# MoodBadge.net
KiCad netlist of a schematic drawn in EAGLE
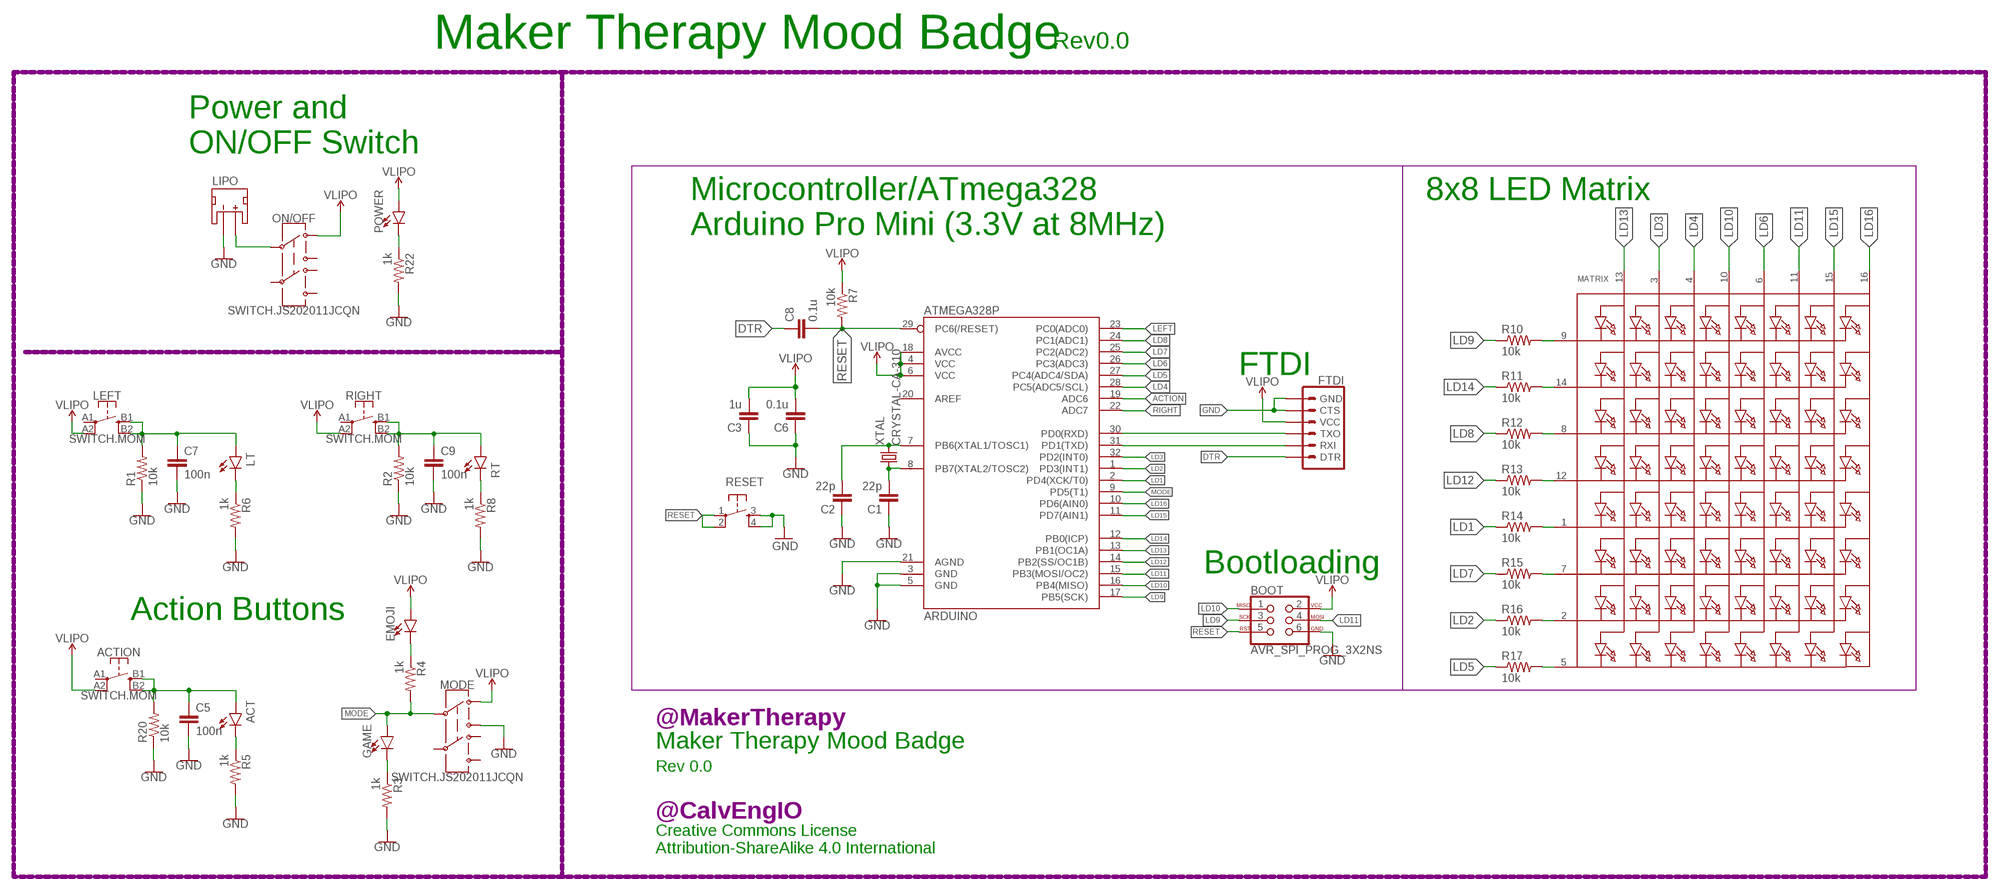
[diagram p0: schematic, sheet 1]

(export (version "E")
  (design (tool "Eeschema 10.0.6"))
  (components
    (comp (ref "ACT")
      (value "LED0603")
      (footprint "eagle-import:LED-0603")
      (libsource (lib "eagle-import") (part "LED0603"))
    )
    (comp (ref "ACTION")
      (value "SWITCH.MOM")
      (footprint "eagle-import:TACTILE_SWITCH_SMD_6.2MM_TALL")
      (libsource (lib "eagle-import") (part "SWITCH.MOM"))
    )
    (comp (ref "ARDUINO")
      (value "ATMEGA328P")
      (footprint "eagle-import:TQFP32-08")
      (libsource (lib "eagle-import") (part "ATMEGA328_SMT-OHMOD"))
    )
    (comp (ref "BOOT")
      (value "AVR_SPI_PROG_3X2NS")
      (footprint "eagle-import:2X3-NS")
      (libsource (lib "eagle-import") (part "AVR_SPI_PROG_3X2NS"))
    )
    (comp (ref "C1")
      (value "22p")
      (footprint "eagle-import:C0402")
      (libsource (lib "eagle-import") (part "CAPACITOR0402"))
    )
    (comp (ref "C2")
      (value "22p")
      (footprint "eagle-import:C0402")
      (libsource (lib "eagle-import") (part "CAPACITOR0402"))
    )
    (comp (ref "C3")
      (value "1u")
      (footprint "eagle-import:C0402")
      (libsource (lib "eagle-import") (part "CAPACITOR0402"))
    )
    (comp (ref "C5")
      (value "100n")
      (footprint "eagle-import:C0402")
      (libsource (lib "eagle-import") (part "CAPACITOR0402"))
    )
    (comp (ref "C6")
      (value "0.1u")
      (footprint "eagle-import:C0402")
      (libsource (lib "eagle-import") (part "CAPACITOR0402"))
    )
    (comp (ref "C7")
      (value "100n")
      (footprint "eagle-import:C0402")
      (libsource (lib "eagle-import") (part "CAPACITOR0402"))
    )
    (comp (ref "C8")
      (value "0.1u")
      (footprint "eagle-import:C0402")
      (libsource (lib "eagle-import") (part "C-EUC0402"))
    )
    (comp (ref "C9")
      (value "100n")
      (footprint "eagle-import:C0402")
      (libsource (lib "eagle-import") (part "CAPACITOR0402"))
    )
    (comp (ref "EMOJI")
      (value "LED0603")
      (footprint "eagle-import:LED-0603")
      (libsource (lib "eagle-import") (part "LED0603"))
    )
    (comp (ref "FTDI")
      (value "6_PIN_SERIAL_TARGETSILK")
      (footprint "eagle-import:6_PIN_SERIAL_TARGET_SIDE_W_SILK")
      (libsource (lib "eagle-import") (part "6_PIN_SERIAL_TARGETSILK"))
    )
    (comp (ref "GAME")
      (value "LED0603")
      (footprint "eagle-import:LED-0603")
      (libsource (lib "eagle-import") (part "LED0603"))
    )
    (comp (ref "LEFT")
      (value "SWITCH.MOM")
      (footprint "eagle-import:TACTILE_SWITCH_SMD_6.2MM_TALL")
      (libsource (lib "eagle-import") (part "SWITCH.MOM"))
    )
    (comp (ref "LIPO")
      (value "JST_2MM_MALE")
      (footprint "eagle-import:JST-2-SMD")
      (libsource (lib "eagle-import") (part "JST_2MM_MALE"))
    )
    (comp (ref "LT")
      (value "LED0603")
      (footprint "eagle-import:LED-0603")
      (libsource (lib "eagle-import") (part "LED0603"))
    )
    (comp (ref "MATRIX")
      (value "SEGMENT_8X8_ROWCATHODEM12A881UR")
      (footprint "eagle-import:SEGMENT_BL-M12A881UR")
      (libsource (lib "eagle-import") (part "SEGMENT_8X8_ROWCATHODEM12A881UR"))
    )
    (comp (ref "MODE")
      (value "SWITCH.JS202011JCQN")
      (footprint "eagle-import:SWITCH.00")
      (libsource (lib "eagle-import") (part "SWITCH.JS202011JCQN"))
    )
    (comp (ref "ON/OFF")
      (value "SWITCH.JS202011JCQN")
      (footprint "eagle-import:SWITCH.00")
      (libsource (lib "eagle-import") (part "SWITCH.JS202011JCQN"))
    )
    (comp (ref "POWER")
      (value "LED5MM")
      (footprint "eagle-import:LED_5MM")
      (libsource (lib "eagle-import") (part "LED5MM"))
    )
    (comp (ref "R1")
      (value "10k")
      (footprint "eagle-import:R0402")
      (libsource (lib "eagle-import") (part "RESISTOR0402"))
    )
    (comp (ref "R2")
      (value "10k")
      (footprint "eagle-import:R0402")
      (libsource (lib "eagle-import") (part "RESISTOR0402"))
    )
    (comp (ref "R3")
      (value "1k")
      (footprint "eagle-import:R0402")
      (libsource (lib "eagle-import") (part "RESISTOR0402"))
    )
    (comp (ref "R4")
      (value "1k")
      (footprint "eagle-import:R0402")
      (libsource (lib "eagle-import") (part "RESISTOR0402"))
    )
    (comp (ref "R5")
      (value "1k")
      (footprint "eagle-import:R0402")
      (libsource (lib "eagle-import") (part "RESISTOR0402"))
    )
    (comp (ref "R6")
      (value "1k")
      (footprint "eagle-import:R0402")
      (libsource (lib "eagle-import") (part "RESISTOR0402"))
    )
    (comp (ref "R7")
      (value "10k")
      (footprint "eagle-import:R0402")
      (libsource (lib "eagle-import") (part "RESISTOR0402"))
    )
    (comp (ref "R8")
      (value "1k")
      (footprint "eagle-import:R0402")
      (libsource (lib "eagle-import") (part "RESISTOR0402"))
    )
    (comp (ref "R10")
      (value "10k")
      (footprint "eagle-import:R0402")
      (libsource (lib "eagle-import") (part "RESISTOR0402"))
    )
    (comp (ref "R11")
      (value "10k")
      (footprint "eagle-import:R0402")
      (libsource (lib "eagle-import") (part "RESISTOR0402"))
    )
    (comp (ref "R12")
      (value "10k")
      (footprint "eagle-import:R0402")
      (libsource (lib "eagle-import") (part "RESISTOR0402"))
    )
    (comp (ref "R13")
      (value "10k")
      (footprint "eagle-import:R0402")
      (libsource (lib "eagle-import") (part "RESISTOR0402"))
    )
    (comp (ref "R14")
      (value "10k")
      (footprint "eagle-import:R0402")
      (libsource (lib "eagle-import") (part "RESISTOR0402"))
    )
    (comp (ref "R15")
      (value "10k")
      (footprint "eagle-import:R0402")
      (libsource (lib "eagle-import") (part "RESISTOR0402"))
    )
    (comp (ref "R16")
      (value "10k")
      (footprint "eagle-import:R0402")
      (libsource (lib "eagle-import") (part "RESISTOR0402"))
    )
    (comp (ref "R17")
      (value "10k")
      (footprint "eagle-import:R0402")
      (libsource (lib "eagle-import") (part "RESISTOR0402"))
    )
    (comp (ref "R20")
      (value "10k")
      (footprint "eagle-import:R0402")
      (libsource (lib "eagle-import") (part "RESISTOR0402"))
    )
    (comp (ref "R22")
      (value "1k")
      (footprint "eagle-import:R0402")
      (libsource (lib "eagle-import") (part "RESISTOR0402"))
    )
    (comp (ref "RESET")
      (value "BUTTON-PTS830GG140")
      (footprint "eagle-import:BUTTON-GULLWING")
      (libsource (lib "eagle-import") (part "BUTTON-PTS830GG140"))
    )
    (comp (ref "RIGHT")
      (value "SWITCH.MOM")
      (footprint "eagle-import:TACTILE_SWITCH_SMD_6.2MM_TALL")
      (libsource (lib "eagle-import") (part "SWITCH.MOM"))
    )
    (comp (ref "RT")
      (value "LED0603")
      (footprint "eagle-import:LED-0603")
      (libsource (lib "eagle-import") (part "LED0603"))
    )
    (comp (ref "U$8")
      (value "CALVENGIO_HANDLEHANDLE.05")
      (footprint "eagle-import:CALVENGIO_HANDLE.05")
      (libsource (lib "eagle-import") (part "CALVENGIO_HANDLEHANDLE.05"))
    )
    (comp (ref "U$10")
      (value "MAKERTHERAPY.HANDLEMAKERTHERAPY.HANDLE.175")
      (footprint "eagle-import:MAKERTHERAPY.HANDLE.175")
      (libsource (lib "eagle-import") (part "MAKERTHERAPY.HANDLEMAKERTHERAPY.HANDLE.175"))
    )
    (comp (ref "XTAL")
      (value "CRYSTAL-CA-310")
      (footprint "eagle-import:CA-301")
      (libsource (lib "eagle-import") (part "CRYSTAL-CA-310"))
    )
  )
  (nets
    (net (code "1") (name "ACTION") (class "Default")
      (node (ref "ACT") (pin "A") (pinfunction "A_A") (pintype "passive"))
      (node (ref "ACTION") (pin "B1") (pinfunction "3_B1") (pintype "passive"))
      (node (ref "ACTION") (pin "B2") (pinfunction "4_B2") (pintype "passive"))
      (node (ref "ARDUINO") (pin "19") (pinfunction "ADC6_19") (pintype "bidirectional"))
      (node (ref "C5") (pin "1") (pinfunction "1_1") (pintype "passive"))
      (node (ref "R20") (pin "2") (pinfunction "2_2") (pintype "passive"))
    )
    (net (code "2") (name "DTR") (class "Default")
      (node (ref "C8") (pin "1") (pinfunction "1_1") (pintype "passive"))
      (node (ref "FTDI") (pin "P$1") (pinfunction "DTR_P$1") (pintype "passive"))
    )
    (net (code "3") (name "GND") (class "Default")
      (node (ref "ARDUINO") (pin "21") (pinfunction "AGND_21") (pintype "bidirectional"))
      (node (ref "ARDUINO") (pin "3") (pinfunction "GND_3") (pintype "bidirectional"))
      (node (ref "ARDUINO") (pin "5") (pinfunction "GND_5") (pintype "bidirectional"))
      (node (ref "BOOT") (pin "6") (pinfunction "6_6") (pintype "passive"))
      (node (ref "C1") (pin "1") (pinfunction "1_1") (pintype "passive"))
      (node (ref "C2") (pin "1") (pinfunction "1_1") (pintype "passive"))
      (node (ref "C3") (pin "1") (pinfunction "1_1") (pintype "passive"))
      (node (ref "C5") (pin "2") (pinfunction "2_2") (pintype "passive"))
      (node (ref "C6") (pin "1") (pinfunction "1_1") (pintype "passive"))
      (node (ref "C7") (pin "2") (pinfunction "2_2") (pintype "passive"))
      (node (ref "C9") (pin "2") (pinfunction "2_2") (pintype "passive"))
      (node (ref "FTDI") (pin "P$5") (pinfunction "CTS_P$5") (pintype "passive"))
      (node (ref "FTDI") (pin "P$6") (pinfunction "GND_P$6") (pintype "passive"))
      (node (ref "LIPO") (pin "1") (pinfunction "-_1") (pintype "bidirectional"))
      (node (ref "MODE") (pin "3") (pinfunction "3_3") (pintype "bidirectional"))
      (node (ref "R1") (pin "1") (pinfunction "1_1") (pintype "passive"))
      (node (ref "R2") (pin "1") (pinfunction "1_1") (pintype "passive"))
      (node (ref "R20") (pin "1") (pinfunction "1_1") (pintype "passive"))
      (node (ref "R22") (pin "2") (pinfunction "2_2") (pintype "passive"))
      (node (ref "R3") (pin "2") (pinfunction "2_2") (pintype "passive"))
      (node (ref "R5") (pin "2") (pinfunction "2_2") (pintype "passive"))
      (node (ref "R6") (pin "2") (pinfunction "2_2") (pintype "passive"))
      (node (ref "R8") (pin "2") (pinfunction "2_2") (pintype "passive"))
      (node (ref "RESET") (pin "3") (pinfunction "3_3") (pintype "passive"))
      (node (ref "RESET") (pin "4") (pinfunction "4_4") (pintype "passive"))
    )
    (net (code "4") (name "LD1") (class "Default")
      (node (ref "ARDUINO") (pin "2") (pinfunction "PD4(XCK/T0)_2") (pintype "bidirectional"))
      (node (ref "R14") (pin "1") (pinfunction "1_1") (pintype "passive"))
    )
    (net (code "5") (name "LD2") (class "Default")
      (node (ref "ARDUINO") (pin "1") (pinfunction "PD3(INT1)_1") (pintype "bidirectional"))
      (node (ref "R16") (pin "1") (pinfunction "1_1") (pintype "passive"))
    )
    (net (code "6") (name "LD3") (class "Default")
      (node (ref "ARDUINO") (pin "32") (pinfunction "PD2(INT0)_32") (pintype "bidirectional"))
      (node (ref "MATRIX") (pin "3") (pinfunction "A2_3") (pintype "bidirectional"))
    )
    (net (code "7") (name "LD4") (class "Default")
      (node (ref "ARDUINO") (pin "28") (pinfunction "PC5(ADC5/SCL)_28") (pintype "bidirectional"))
      (node (ref "MATRIX") (pin "4") (pinfunction "A3_4") (pintype "bidirectional"))
    )
    (net (code "8") (name "LD5") (class "Default")
      (node (ref "ARDUINO") (pin "27") (pinfunction "PC4(ADC4/SDA)_27") (pintype "bidirectional"))
      (node (ref "R17") (pin "1") (pinfunction "1_1") (pintype "passive"))
    )
    (net (code "9") (name "LD6") (class "Default")
      (node (ref "ARDUINO") (pin "26") (pinfunction "PC3(ADC3)_26") (pintype "bidirectional"))
      (node (ref "MATRIX") (pin "6") (pinfunction "A5_6") (pintype "bidirectional"))
    )
    (net (code "10") (name "LD7") (class "Default")
      (node (ref "ARDUINO") (pin "25") (pinfunction "PC2(ADC2)_25") (pintype "bidirectional"))
      (node (ref "R15") (pin "1") (pinfunction "1_1") (pintype "passive"))
    )
    (net (code "11") (name "LD8") (class "Default")
      (node (ref "ARDUINO") (pin "24") (pinfunction "PC1(ADC1)_24") (pintype "bidirectional"))
      (node (ref "R12") (pin "1") (pinfunction "1_1") (pintype "passive"))
    )
    (net (code "12") (name "LD9") (class "Default")
      (node (ref "ARDUINO") (pin "17") (pinfunction "PB5(SCK)_17") (pintype "bidirectional"))
      (node (ref "BOOT") (pin "3") (pinfunction "3_3") (pintype "passive"))
      (node (ref "R10") (pin "1") (pinfunction "1_1") (pintype "passive"))
    )
    (net (code "13") (name "LD10") (class "Default")
      (node (ref "ARDUINO") (pin "16") (pinfunction "PB4(MISO)_16") (pintype "bidirectional"))
      (node (ref "BOOT") (pin "1") (pinfunction "1_1") (pintype "passive"))
      (node (ref "MATRIX") (pin "10") (pinfunction "A4_10") (pintype "bidirectional"))
    )
    (net (code "14") (name "LD11") (class "Default")
      (node (ref "ARDUINO") (pin "15") (pinfunction "PB3(MOSI/OC2)_15") (pintype "bidirectional"))
      (node (ref "BOOT") (pin "4") (pinfunction "4_4") (pintype "passive"))
      (node (ref "MATRIX") (pin "11") (pinfunction "A6_11") (pintype "bidirectional"))
    )
    (net (code "15") (name "LD12") (class "Default")
      (node (ref "ARDUINO") (pin "14") (pinfunction "PB2(SS/OC1B)_14") (pintype "bidirectional"))
      (node (ref "R13") (pin "1") (pinfunction "1_1") (pintype "passive"))
    )
    (net (code "16") (name "LD13") (class "Default")
      (node (ref "ARDUINO") (pin "13") (pinfunction "PB1(OC1A)_13") (pintype "bidirectional"))
      (node (ref "MATRIX") (pin "13") (pinfunction "A1_13") (pintype "bidirectional"))
    )
    (net (code "17") (name "LD14") (class "Default")
      (node (ref "ARDUINO") (pin "12") (pinfunction "PB0(ICP)_12") (pintype "bidirectional"))
      (node (ref "R11") (pin "1") (pinfunction "1_1") (pintype "passive"))
    )
    (net (code "18") (name "LD15") (class "Default")
      (node (ref "ARDUINO") (pin "11") (pinfunction "PD7(AIN1)_11") (pintype "bidirectional"))
      (node (ref "MATRIX") (pin "15") (pinfunction "A7_15") (pintype "bidirectional"))
    )
    (net (code "19") (name "LD16") (class "Default")
      (node (ref "ARDUINO") (pin "10") (pinfunction "PD6(AIN0)_10") (pintype "bidirectional"))
      (node (ref "MATRIX") (pin "16") (pinfunction "A8_16") (pintype "bidirectional"))
    )
    (net (code "20") (name "LEFT") (class "Default")
      (node (ref "ARDUINO") (pin "23") (pinfunction "PC0(ADC0)_23") (pintype "bidirectional"))
      (node (ref "C7") (pin "1") (pinfunction "1_1") (pintype "passive"))
      (node (ref "LEFT") (pin "B1") (pinfunction "3_B1") (pintype "passive"))
      (node (ref "LEFT") (pin "B2") (pinfunction "4_B2") (pintype "passive"))
      (node (ref "LT") (pin "A") (pinfunction "A_A") (pintype "passive"))
      (node (ref "R1") (pin "2") (pinfunction "2_2") (pintype "passive"))
    )
    (net (code "21") (name "MODE") (class "Default")
      (node (ref "ARDUINO") (pin "9") (pinfunction "PD5(T1)_9") (pintype "bidirectional"))
      (node (ref "GAME") (pin "A") (pinfunction "A_A") (pintype "passive"))
      (node (ref "MODE") (pin "2") (pinfunction "2_2") (pintype "bidirectional"))
      (node (ref "R4") (pin "2") (pinfunction "2_2") (pintype "passive"))
    )
    (net (code "22") (name "Net-(ACT-PadC)") (class "Default")
      (node (ref "ACT") (pin "C") (pinfunction "C_C") (pintype "passive"))
      (node (ref "R5") (pin "1") (pinfunction "1_1") (pintype "passive"))
    )
    (net (code "23") (name "Net-(ARDUINO-PB6(XTAL1{slash}TOSC1))") (class "Default")
      (node (ref "ARDUINO") (pin "7") (pinfunction "PB6(XTAL1/TOSC1)_7") (pintype "bidirectional"))
      (node (ref "C2") (pin "2") (pinfunction "2_2") (pintype "passive"))
      (node (ref "XTAL") (pin "2") (pinfunction "2_2") (pintype "passive"))
    )
    (net (code "24") (name "Net-(ARDUINO-PB7(XTAL2{slash}TOSC2))") (class "Default")
      (node (ref "ARDUINO") (pin "8") (pinfunction "PB7(XTAL2/TOSC2)_8") (pintype "bidirectional"))
      (node (ref "C1") (pin "2") (pinfunction "2_2") (pintype "passive"))
      (node (ref "XTAL") (pin "1") (pinfunction "1_1") (pintype "passive"))
    )
    (net (code "25") (name "Net-(ARDUINO-PD0(RXD))") (class "Default")
      (node (ref "ARDUINO") (pin "30") (pinfunction "PD0(RXD)_30") (pintype "bidirectional"))
      (node (ref "FTDI") (pin "P$2") (pinfunction "TXO_P$2") (pintype "passive"))
    )
    (net (code "26") (name "Net-(ARDUINO-PD1(TXD))") (class "Default")
      (node (ref "ARDUINO") (pin "31") (pinfunction "PD1(TXD)_31") (pintype "bidirectional"))
      (node (ref "FTDI") (pin "P$3") (pinfunction "RXI_P$3") (pintype "passive"))
    )
    (net (code "27") (name "Net-(EMOJI-PadC)") (class "Default")
      (node (ref "EMOJI") (pin "C") (pinfunction "C_C") (pintype "passive"))
      (node (ref "R4") (pin "1") (pinfunction "1_1") (pintype "passive"))
    )
    (net (code "28") (name "Net-(GAME-PadC)") (class "Default")
      (node (ref "GAME") (pin "C") (pinfunction "C_C") (pintype "passive"))
      (node (ref "R3") (pin "1") (pinfunction "1_1") (pintype "passive"))
    )
    (net (code "29") (name "Net-(LIPO-+)") (class "Default")
      (node (ref "LIPO") (pin "2") (pinfunction "+_2") (pintype "bidirectional"))
      (node (ref "ON/OFF") (pin "2") (pinfunction "2_2") (pintype "bidirectional"))
    )
    (net (code "30") (name "Net-(LT-PadC)") (class "Default")
      (node (ref "LT") (pin "C") (pinfunction "C_C") (pintype "passive"))
      (node (ref "R6") (pin "1") (pinfunction "1_1") (pintype "passive"))
    )
    (net (code "31") (name "Net-(MATRIX-K1)") (class "Default")
      (node (ref "MATRIX") (pin "9") (pinfunction "K1_9") (pintype "bidirectional"))
      (node (ref "R10") (pin "2") (pinfunction "2_2") (pintype "passive"))
    )
    (net (code "32") (name "Net-(MATRIX-K2)") (class "Default")
      (node (ref "MATRIX") (pin "14") (pinfunction "K2_14") (pintype "bidirectional"))
      (node (ref "R11") (pin "2") (pinfunction "2_2") (pintype "passive"))
    )
    (net (code "33") (name "Net-(MATRIX-K3)") (class "Default")
      (node (ref "MATRIX") (pin "8") (pinfunction "K3_8") (pintype "bidirectional"))
      (node (ref "R12") (pin "2") (pinfunction "2_2") (pintype "passive"))
    )
    (net (code "34") (name "Net-(MATRIX-K4)") (class "Default")
      (node (ref "MATRIX") (pin "12") (pinfunction "K4_12") (pintype "bidirectional"))
      (node (ref "R13") (pin "2") (pinfunction "2_2") (pintype "passive"))
    )
    (net (code "35") (name "Net-(MATRIX-K5)") (class "Default")
      (node (ref "MATRIX") (pin "1") (pinfunction "K5_1") (pintype "bidirectional"))
      (node (ref "R14") (pin "2") (pinfunction "2_2") (pintype "passive"))
    )
    (net (code "36") (name "Net-(MATRIX-K6)") (class "Default")
      (node (ref "MATRIX") (pin "7") (pinfunction "K6_7") (pintype "bidirectional"))
      (node (ref "R15") (pin "2") (pinfunction "2_2") (pintype "passive"))
    )
    (net (code "37") (name "Net-(MATRIX-K7)") (class "Default")
      (node (ref "MATRIX") (pin "2") (pinfunction "K7_2") (pintype "bidirectional"))
      (node (ref "R16") (pin "2") (pinfunction "2_2") (pintype "passive"))
    )
    (net (code "38") (name "Net-(MATRIX-K8)") (class "Default")
      (node (ref "MATRIX") (pin "5") (pinfunction "K8_5") (pintype "bidirectional"))
      (node (ref "R17") (pin "2") (pinfunction "2_2") (pintype "passive"))
    )
    (net (code "39") (name "Net-(POWER-C)") (class "Default")
      (node (ref "POWER") (pin "K") (pinfunction "C_K") (pintype "passive"))
      (node (ref "R22") (pin "1") (pinfunction "1_1") (pintype "passive"))
    )
    (net (code "40") (name "Net-(R8-Pad1)") (class "Default")
      (node (ref "R8") (pin "1") (pinfunction "1_1") (pintype "passive"))
      (node (ref "RT") (pin "C") (pinfunction "C_C") (pintype "passive"))
    )
    (net (code "41") (name "RESET") (class "Default")
      (node (ref "ARDUINO") (pin "29") (pinfunction "PC6(/RESET)_29") (pintype "bidirectional"))
      (node (ref "BOOT") (pin "5") (pinfunction "5_5") (pintype "passive"))
      (node (ref "C8") (pin "2") (pinfunction "2_2") (pintype "passive"))
      (node (ref "R7") (pin "2") (pinfunction "2_2") (pintype "passive"))
      (node (ref "RESET") (pin "1") (pinfunction "1_1") (pintype "passive"))
      (node (ref "RESET") (pin "2") (pinfunction "2_2") (pintype "passive"))
    )
    (net (code "42") (name "RIGHT") (class "Default")
      (node (ref "ARDUINO") (pin "22") (pinfunction "ADC7_22") (pintype "bidirectional"))
      (node (ref "C9") (pin "1") (pinfunction "1_1") (pintype "passive"))
      (node (ref "R2") (pin "2") (pinfunction "2_2") (pintype "passive"))
      (node (ref "RIGHT") (pin "B1") (pinfunction "3_B1") (pintype "passive"))
      (node (ref "RIGHT") (pin "B2") (pinfunction "4_B2") (pintype "passive"))
      (node (ref "RT") (pin "A") (pinfunction "A_A") (pintype "passive"))
    )
    (net (code "43") (name "VLIPO") (class "Default")
      (node (ref "ACTION") (pin "A2") (pinfunction "2_A2") (pintype "passive"))
      (node (ref "ARDUINO") (pin "18") (pinfunction "AVCC_18") (pintype "bidirectional"))
      (node (ref "ARDUINO") (pin "4") (pinfunction "VCC_4") (pintype "bidirectional"))
      (node (ref "ARDUINO") (pin "6") (pinfunction "VCC_6") (pintype "bidirectional"))
      (node (ref "BOOT") (pin "2") (pinfunction "2_2") (pintype "passive"))
      (node (ref "C3") (pin "2") (pinfunction "2_2") (pintype "passive"))
      (node (ref "C6") (pin "2") (pinfunction "2_2") (pintype "passive"))
      (node (ref "EMOJI") (pin "A") (pinfunction "A_A") (pintype "passive"))
      (node (ref "FTDI") (pin "P$4") (pinfunction "VCC_P$4") (pintype "passive"))
      (node (ref "LEFT") (pin "A2") (pinfunction "2_A2") (pintype "passive"))
      (node (ref "MODE") (pin "1") (pinfunction "1_1") (pintype "bidirectional"))
      (node (ref "ON/OFF") (pin "1") (pinfunction "1_1") (pintype "bidirectional"))
      (node (ref "POWER") (pin "A") (pinfunction "A_A") (pintype "passive"))
      (node (ref "R7") (pin "1") (pinfunction "1_1") (pintype "passive"))
      (node (ref "RIGHT") (pin "A2") (pinfunction "2_A2") (pintype "passive"))
    )
    (net (code "44") (name "unconnected-(ACTION-1-PadA1)") (class "Default")
      (node (ref "ACTION") (pin "A1") (pinfunction "1_A1") (pintype "passive"))
    )
    (net (code "45") (name "unconnected-(ARDUINO-AREF-Pad20)") (class "Default")
      (node (ref "ARDUINO") (pin "20") (pinfunction "AREF_20") (pintype "bidirectional"))
    )
    (net (code "46") (name "unconnected-(LEFT-1-PadA1)") (class "Default")
      (node (ref "LEFT") (pin "A1") (pinfunction "1_A1") (pintype "passive"))
    )
    (net (code "47") (name "unconnected-(LIPO-PAD1-PadNC1)") (class "Default")
      (node (ref "LIPO") (pin "NC1") (pinfunction "PAD1_NC1") (pintype "bidirectional"))
    )
    (net (code "48") (name "unconnected-(LIPO-PAD2-PadNC2)") (class "Default")
      (node (ref "LIPO") (pin "NC2") (pinfunction "PAD2_NC2") (pintype "bidirectional"))
    )
    (net (code "49") (name "unconnected-(MODE-Pad5)") (class "Default")
      (node (ref "MODE") (pin "5") (pinfunction "5_5") (pintype "bidirectional"))
    )
    (net (code "50") (name "unconnected-(MODE-Pad6)") (class "Default")
      (node (ref "MODE") (pin "6") (pinfunction "6_6") (pintype "bidirectional"))
    )
    (net (code "51") (name "unconnected-(MODE-Pad7)") (class "Default")
      (node (ref "MODE") (pin "7") (pinfunction "7_7") (pintype "bidirectional"))
    )
    (net (code "52") (name "unconnected-(ON/OFF-Pad3)") (class "Default")
      (node (ref "ON/OFF") (pin "3") (pinfunction "3_3") (pintype "bidirectional"))
    )
    (net (code "53") (name "unconnected-(ON/OFF-Pad5)") (class "Default")
      (node (ref "ON/OFF") (pin "5") (pinfunction "5_5") (pintype "bidirectional"))
    )
    (net (code "54") (name "unconnected-(ON/OFF-Pad6)") (class "Default")
      (node (ref "ON/OFF") (pin "6") (pinfunction "6_6") (pintype "bidirectional"))
    )
    (net (code "55") (name "unconnected-(ON/OFF-Pad7)") (class "Default")
      (node (ref "ON/OFF") (pin "7") (pinfunction "7_7") (pintype "bidirectional"))
    )
    (net (code "56") (name "unconnected-(RIGHT-1-PadA1)") (class "Default")
      (node (ref "RIGHT") (pin "A1") (pinfunction "1_A1") (pintype "passive"))
    )
  )
)
